# WindCharger.net
KiCad netlist of a schematic drawn in Altium Designer
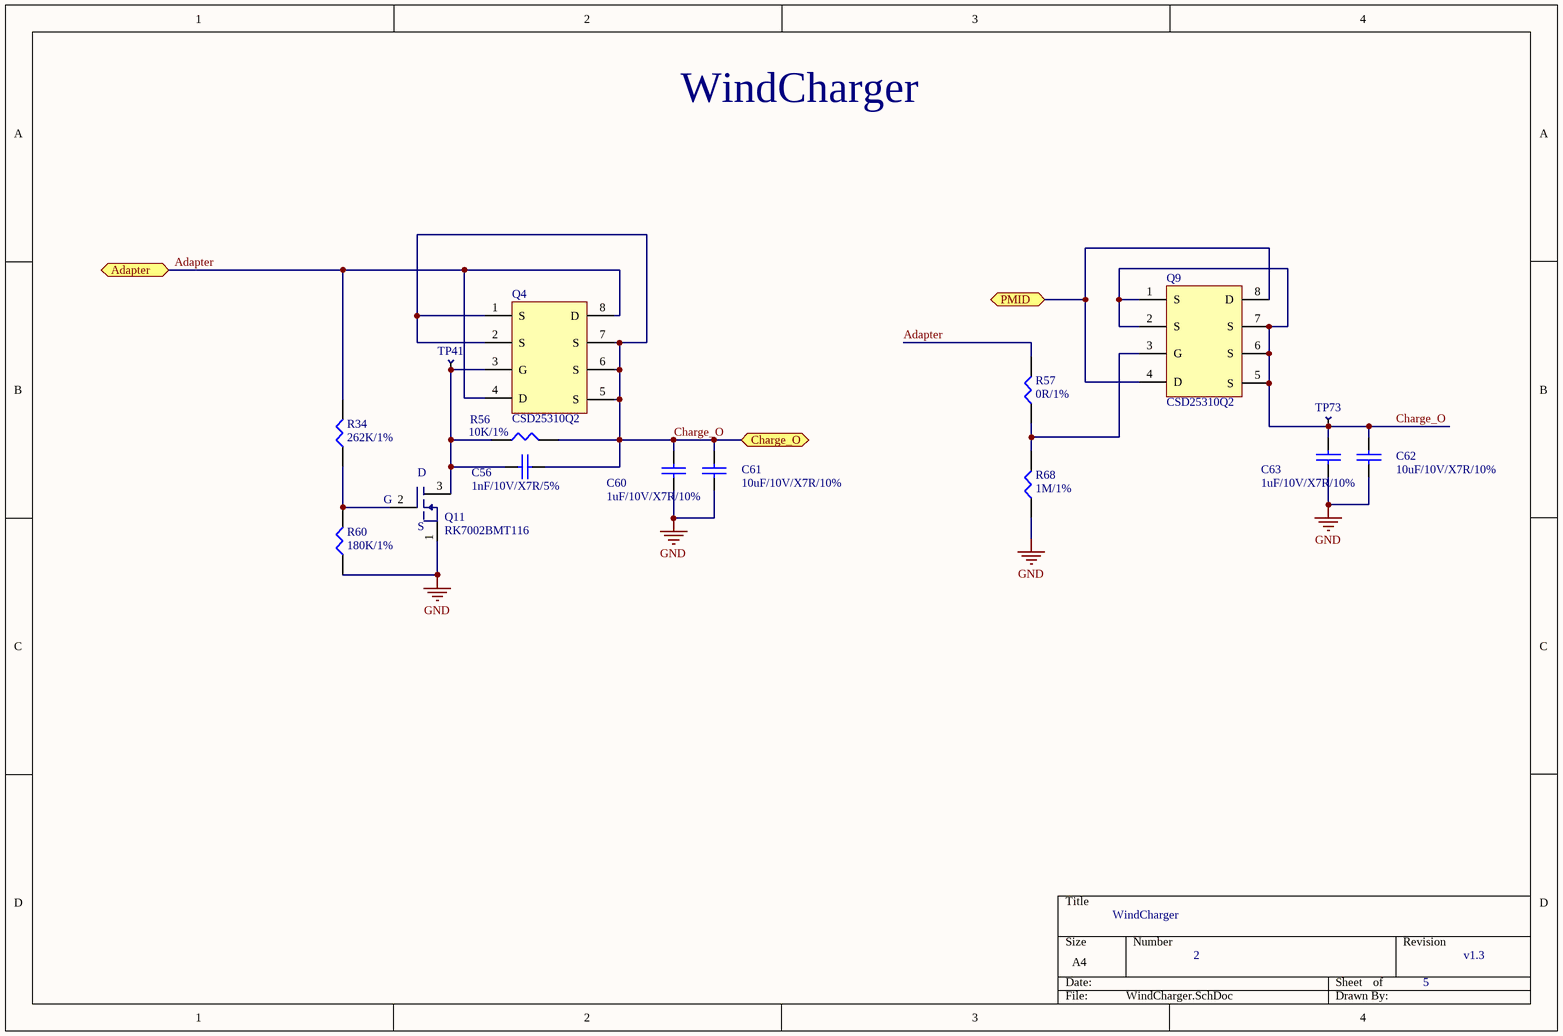
[diagram p0: WindCharger.SchDoc]

(export (version "E")
  (design (tool "Eeschema 10.0.6"))
  (components
    (comp (ref "C56")
      (value "1nF/10V/X7R/5%")
      (footprint "0402C")
      (description "厂家：Murata，型号：GRM1555C1H102JA01D")
      (libsource (lib "*") (part "CAP"))
    )
    (comp (ref "C60")
      (value "1uF/10V/X7R/10%")
      (footprint "0402C")
      (description "厂家：Murata，型号：GRM155R61C105KA12D")
      (libsource (lib "*") (part "CAP"))
    )
    (comp (ref "C61")
      (value "10uF/10V/X7R/10%")
      (footprint "0603C")
      (description "厂家：Murata，型号：GRM188R61A106KE69D")
      (libsource (lib "*") (part "CAP"))
    )
    (comp (ref "C62")
      (value "10uF/10V/X7R/10%")
      (footprint "0603C")
      (description "厂家：Murata，型号：GRM188R61A106KE69D")
      (libsource (lib "*") (part "CAP"))
    )
    (comp (ref "C63")
      (value "1uF/10V/X7R/10%")
      (footprint "0402C")
      (description "厂家：Murata，型号：GRM155R61C105KA12D")
      (libsource (lib "*") (part "CAP"))
    )
    (comp (ref "Q4")
      (value "CSD25310Q2")
      (footprint "DQK")
      (description "厂家：TI，型号：   CSD25310Q2")
      (libsource (lib "Amber_Main_Board") (part "CSD25310Q2"))
    )
    (comp (ref "Q9")
      (value "CSD25310Q2")
      (footprint "DQK")
      (description "厂家：TI，型号：   CSD25310Q2")
      (libsource (lib "Amber_Main_Board") (part "CSD25310Q2"))
    )
    (comp (ref "Q11")
      (value "RK7002BMT116")
      (footprint "SOT23")
      (description "厂家：Vishay，型号：RK7002BMT116")
      (libsource (lib "Amber") (part "RK7002BMT116"))
    )
    (comp (ref "R34")
      (value "262K/1%")
      (footprint "0402R")
      (description "厂家：Yageo，型号：RC0402FR-07262KL")
      (libsource (lib "*") (part "RES1"))
    )
    (comp (ref "R56")
      (value "10K/1%")
      (footprint "0402R")
      (description "厂家：Yageo，型号：RC0402FR-0710KL")
      (libsource (lib "*") (part "RES1"))
    )
    (comp (ref "R57")
      (value "0R/1%")
      (footprint "0402R")
      (description "厂家：Yageo，型号：RC0402FR-071ML")
      (libsource (lib "*") (part "RES1"))
    )
    (comp (ref "R60")
      (value "180K/1%")
      (footprint "0402R")
      (description "厂家：Yageo，型号：RC0402FR-07180KL")
      (libsource (lib "*") (part "RES1"))
    )
    (comp (ref "R68")
      (value "1M/1%")
      (footprint "0402R")
      (description "厂家：Yageo，型号：RC0402FR-071ML")
      (libsource (lib "*") (part "RES1"))
    )
    (comp (ref "TP41")
      (value "TEST")
      (footprint "Test Pad")
      (description "Test Point")
      (libsource (lib "Amber") (part "TEST"))
    )
    (comp (ref "TP73")
      (value "TEST")
      (footprint "Test Pad")
      (description "Test Point")
      (libsource (lib "Amber") (part "TEST"))
    )
  )
  (nets
    (net (code "1") (name "/Adapter") (class "Default")
      (node (ref "Q4") (pin "4") (pinfunction "D_4") (pintype "passive"))
      (node (ref "Q4") (pin "8") (pinfunction "D_8") (pintype "passive"))
      (node (ref "R34") (pin "2") (pinfunction "2_2") (pintype "passive"))
      (node (ref "R57") (pin "2") (pinfunction "2_2") (pintype "passive"))
    )
    (net (code "2") (name "/Charge_O") (class "Default")
      (node (ref "C56") (pin "2") (pinfunction "2_2") (pintype "passive"))
      (node (ref "C60") (pin "1") (pinfunction "1_1") (pintype "passive"))
      (node (ref "C61") (pin "1") (pinfunction "1_1") (pintype "passive"))
      (node (ref "C62") (pin "1") (pinfunction "1_1") (pintype "passive"))
      (node (ref "C63") (pin "1") (pinfunction "1_1") (pintype "passive"))
      (node (ref "Q4") (pin "1") (pinfunction "S_1") (pintype "passive"))
      (node (ref "Q4") (pin "2") (pinfunction "S_2") (pintype "passive"))
      (node (ref "Q4") (pin "5") (pinfunction "S_5") (pintype "passive"))
      (node (ref "Q4") (pin "6") (pinfunction "S_6") (pintype "passive"))
      (node (ref "Q4") (pin "7") (pinfunction "S_7") (pintype "passive"))
      (node (ref "Q9") (pin "1") (pinfunction "S_1") (pintype "passive"))
      (node (ref "Q9") (pin "2") (pinfunction "S_2") (pintype "passive"))
      (node (ref "Q9") (pin "5") (pinfunction "S_5") (pintype "passive"))
      (node (ref "Q9") (pin "6") (pinfunction "S_6") (pintype "passive"))
      (node (ref "Q9") (pin "7") (pinfunction "S_7") (pintype "passive"))
      (node (ref "R56") (pin "2") (pinfunction "2_2") (pintype "passive"))
      (node (ref "TP73") (pin "1") (pinfunction "1_1") (pintype "passive"))
    )
    (net (code "3") (name "/PMID") (class "Default")
      (node (ref "Q9") (pin "4") (pinfunction "D_4") (pintype "passive"))
      (node (ref "Q9") (pin "8") (pinfunction "D_8") (pintype "passive"))
    )
    (net (code "4") (name "GND") (class "Default")
      (node (ref "C60") (pin "2") (pinfunction "2_2") (pintype "passive"))
      (node (ref "C61") (pin "2") (pinfunction "2_2") (pintype "passive"))
      (node (ref "C62") (pin "2") (pinfunction "2_2") (pintype "passive"))
      (node (ref "C63") (pin "2") (pinfunction "2_2") (pintype "passive"))
      (node (ref "Q11") (pin "1") (pinfunction "S_1") (pintype "passive"))
      (node (ref "R60") (pin "1") (pinfunction "1_1") (pintype "passive"))
      (node (ref "R68") (pin "1") (pinfunction "1_1") (pintype "passive"))
    )
    (net (code "5") (name "Net-(Q9-G)") (class "Default")
      (node (ref "Q9") (pin "3") (pinfunction "G_3") (pintype "passive"))
      (node (ref "R57") (pin "1") (pinfunction "1_1") (pintype "passive"))
      (node (ref "R68") (pin "2") (pinfunction "2_2") (pintype "passive"))
    )
    (net (code "6") (name "Net-(Q11-D)") (class "Default")
      (node (ref "C56") (pin "1") (pinfunction "1_1") (pintype "passive"))
      (node (ref "Q11") (pin "3") (pinfunction "D_3") (pintype "passive"))
      (node (ref "Q4") (pin "3") (pinfunction "G_3") (pintype "passive"))
      (node (ref "R56") (pin "1") (pinfunction "1_1") (pintype "passive"))
      (node (ref "TP41") (pin "1") (pinfunction "1_1") (pintype "passive"))
    )
    (net (code "7") (name "Net-(Q11-G)") (class "Default")
      (node (ref "Q11") (pin "2") (pinfunction "G_2") (pintype "passive"))
      (node (ref "R34") (pin "1") (pinfunction "1_1") (pintype "passive"))
      (node (ref "R60") (pin "2") (pinfunction "2_2") (pintype "passive"))
    )
  )
)
